# S140044_NOAA_TOWFISH.net
KiCad netlist of a schematic drawn in EAGLE
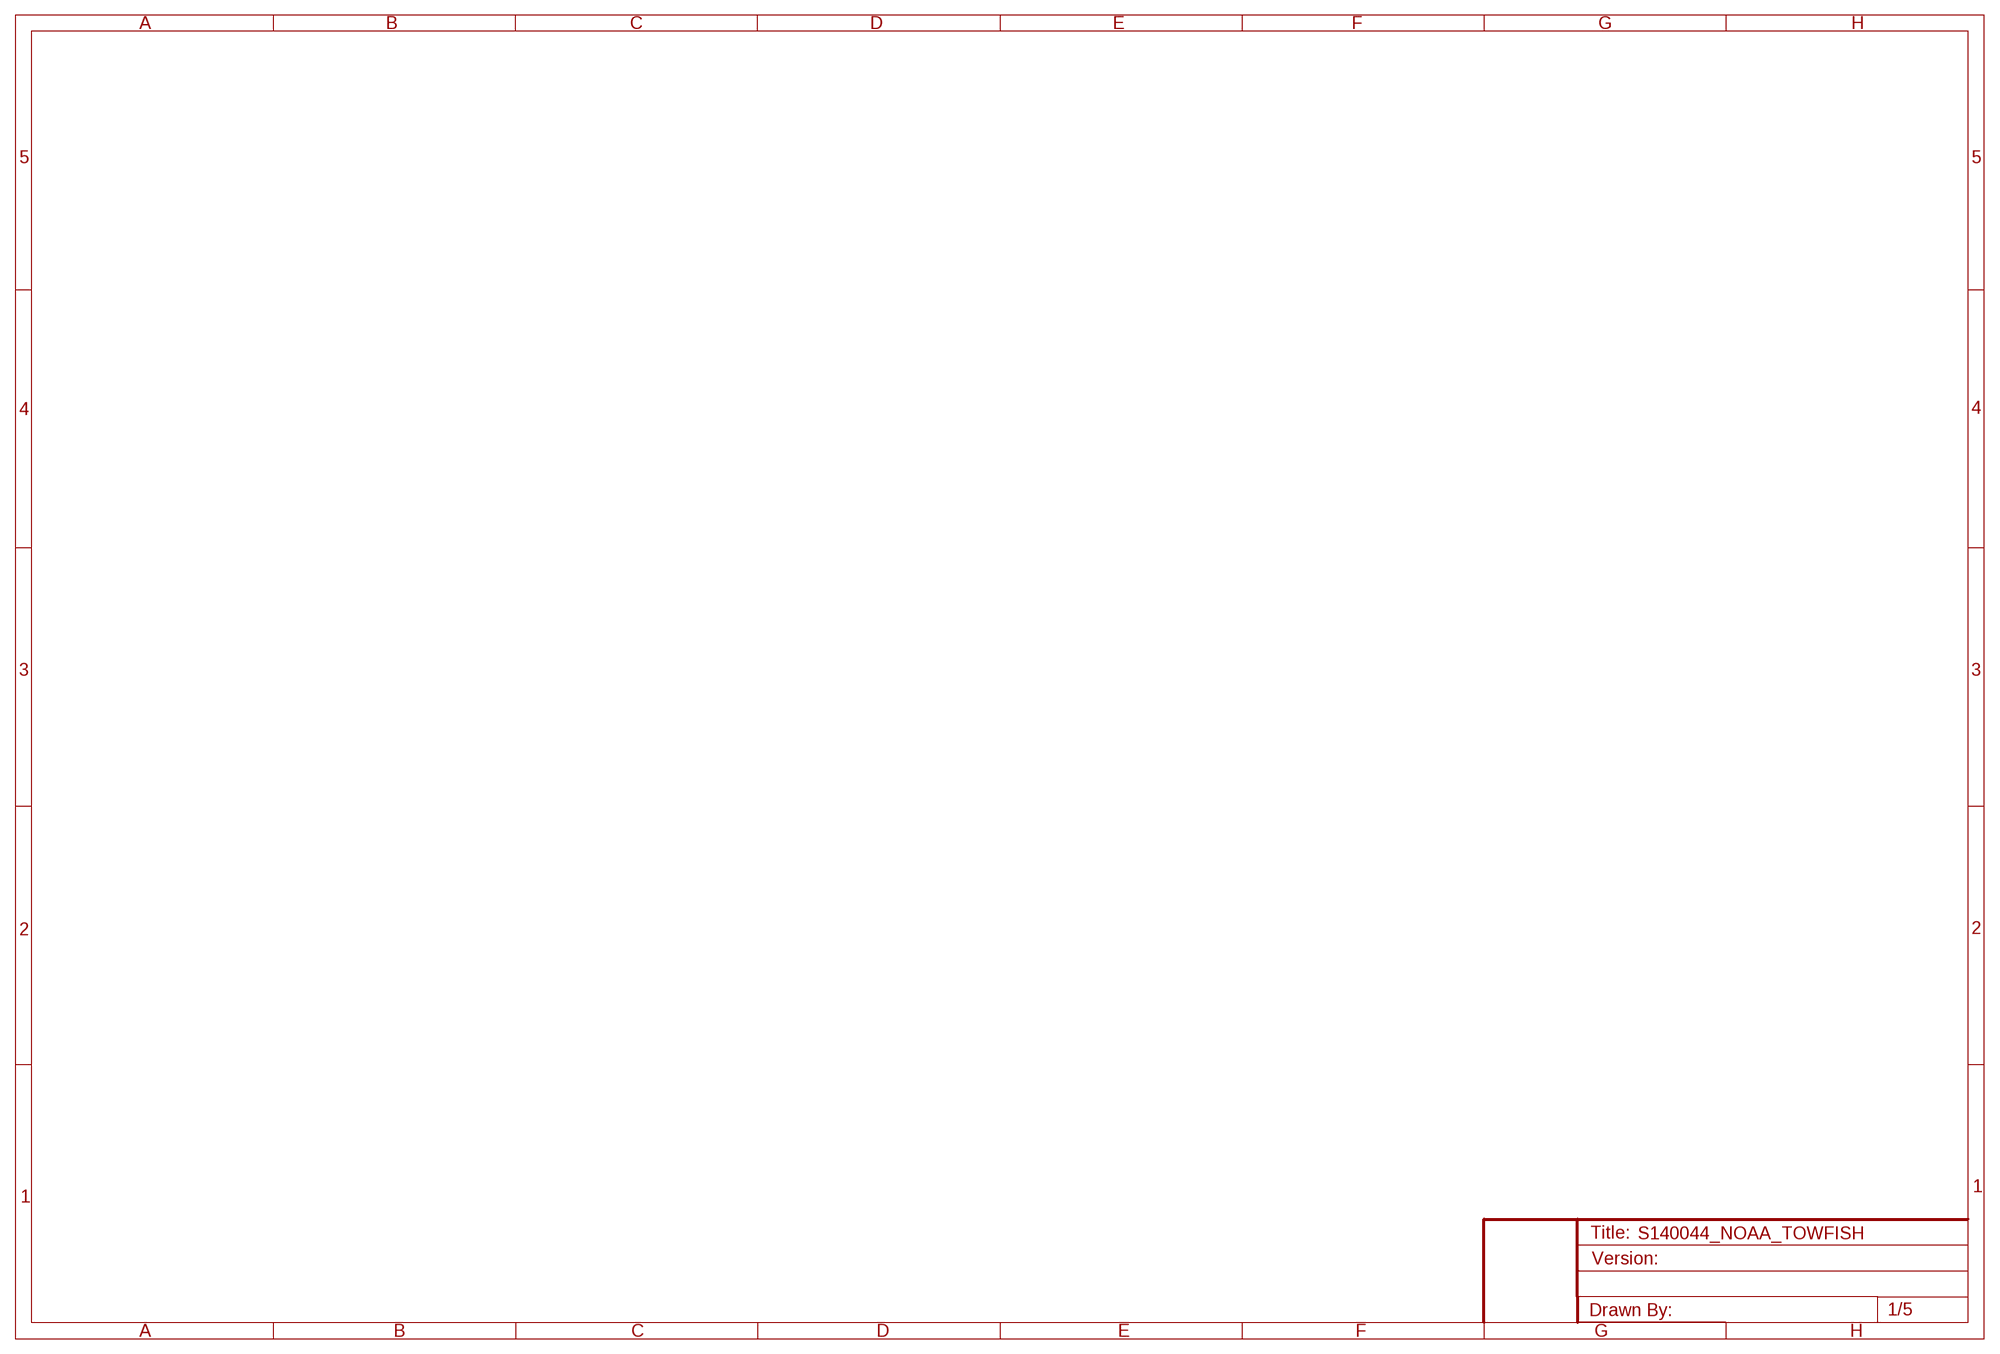
[diagram p0: schematic, sheet 1]
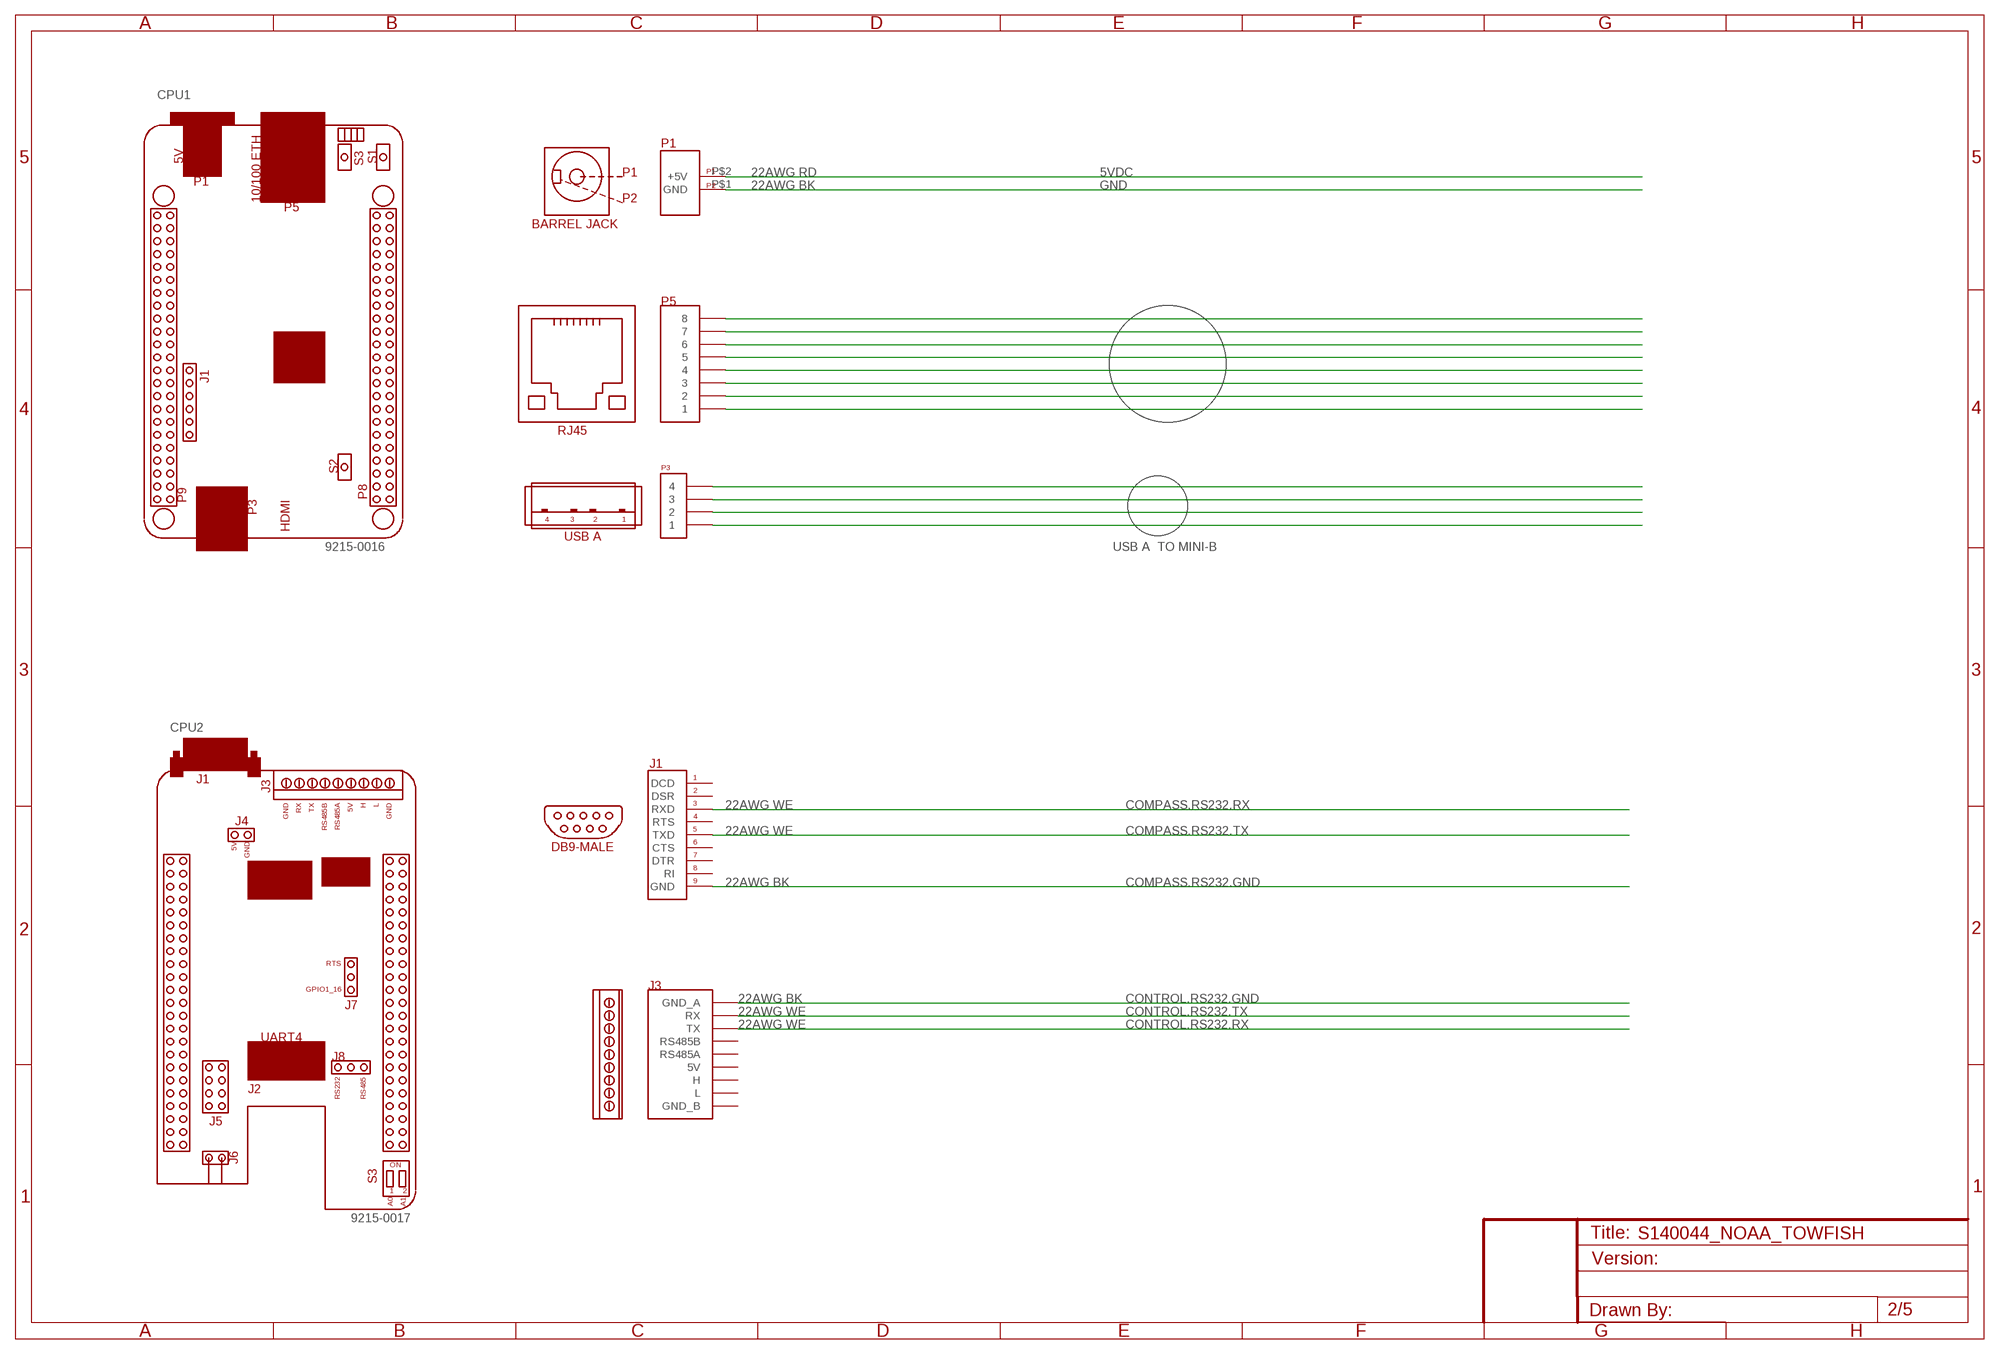
[diagram p1: schematic, sheet 2]
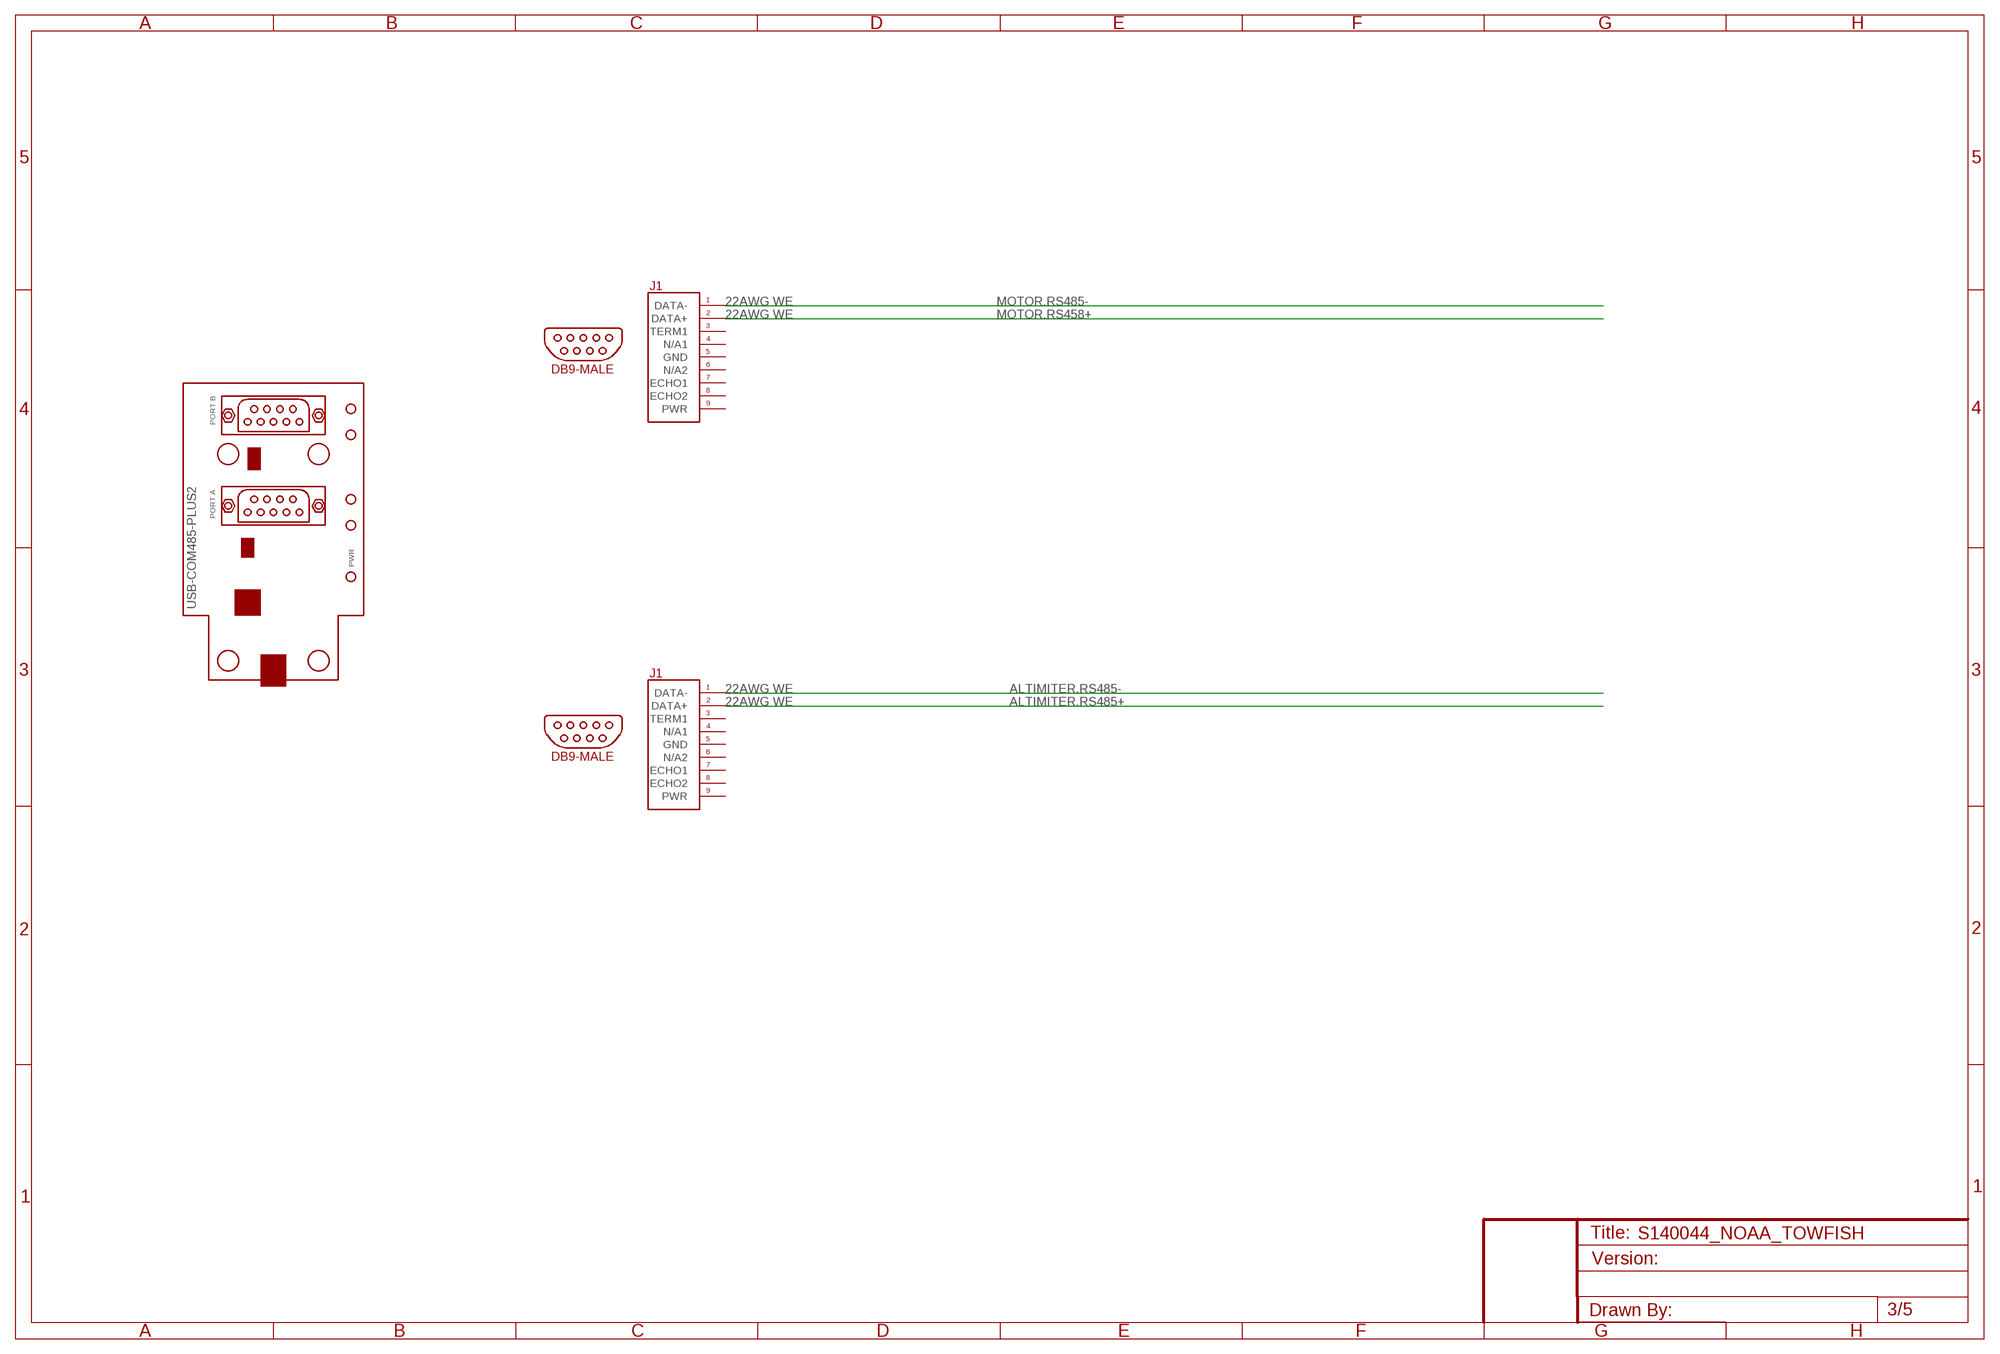
[diagram p2: schematic, sheet 3]
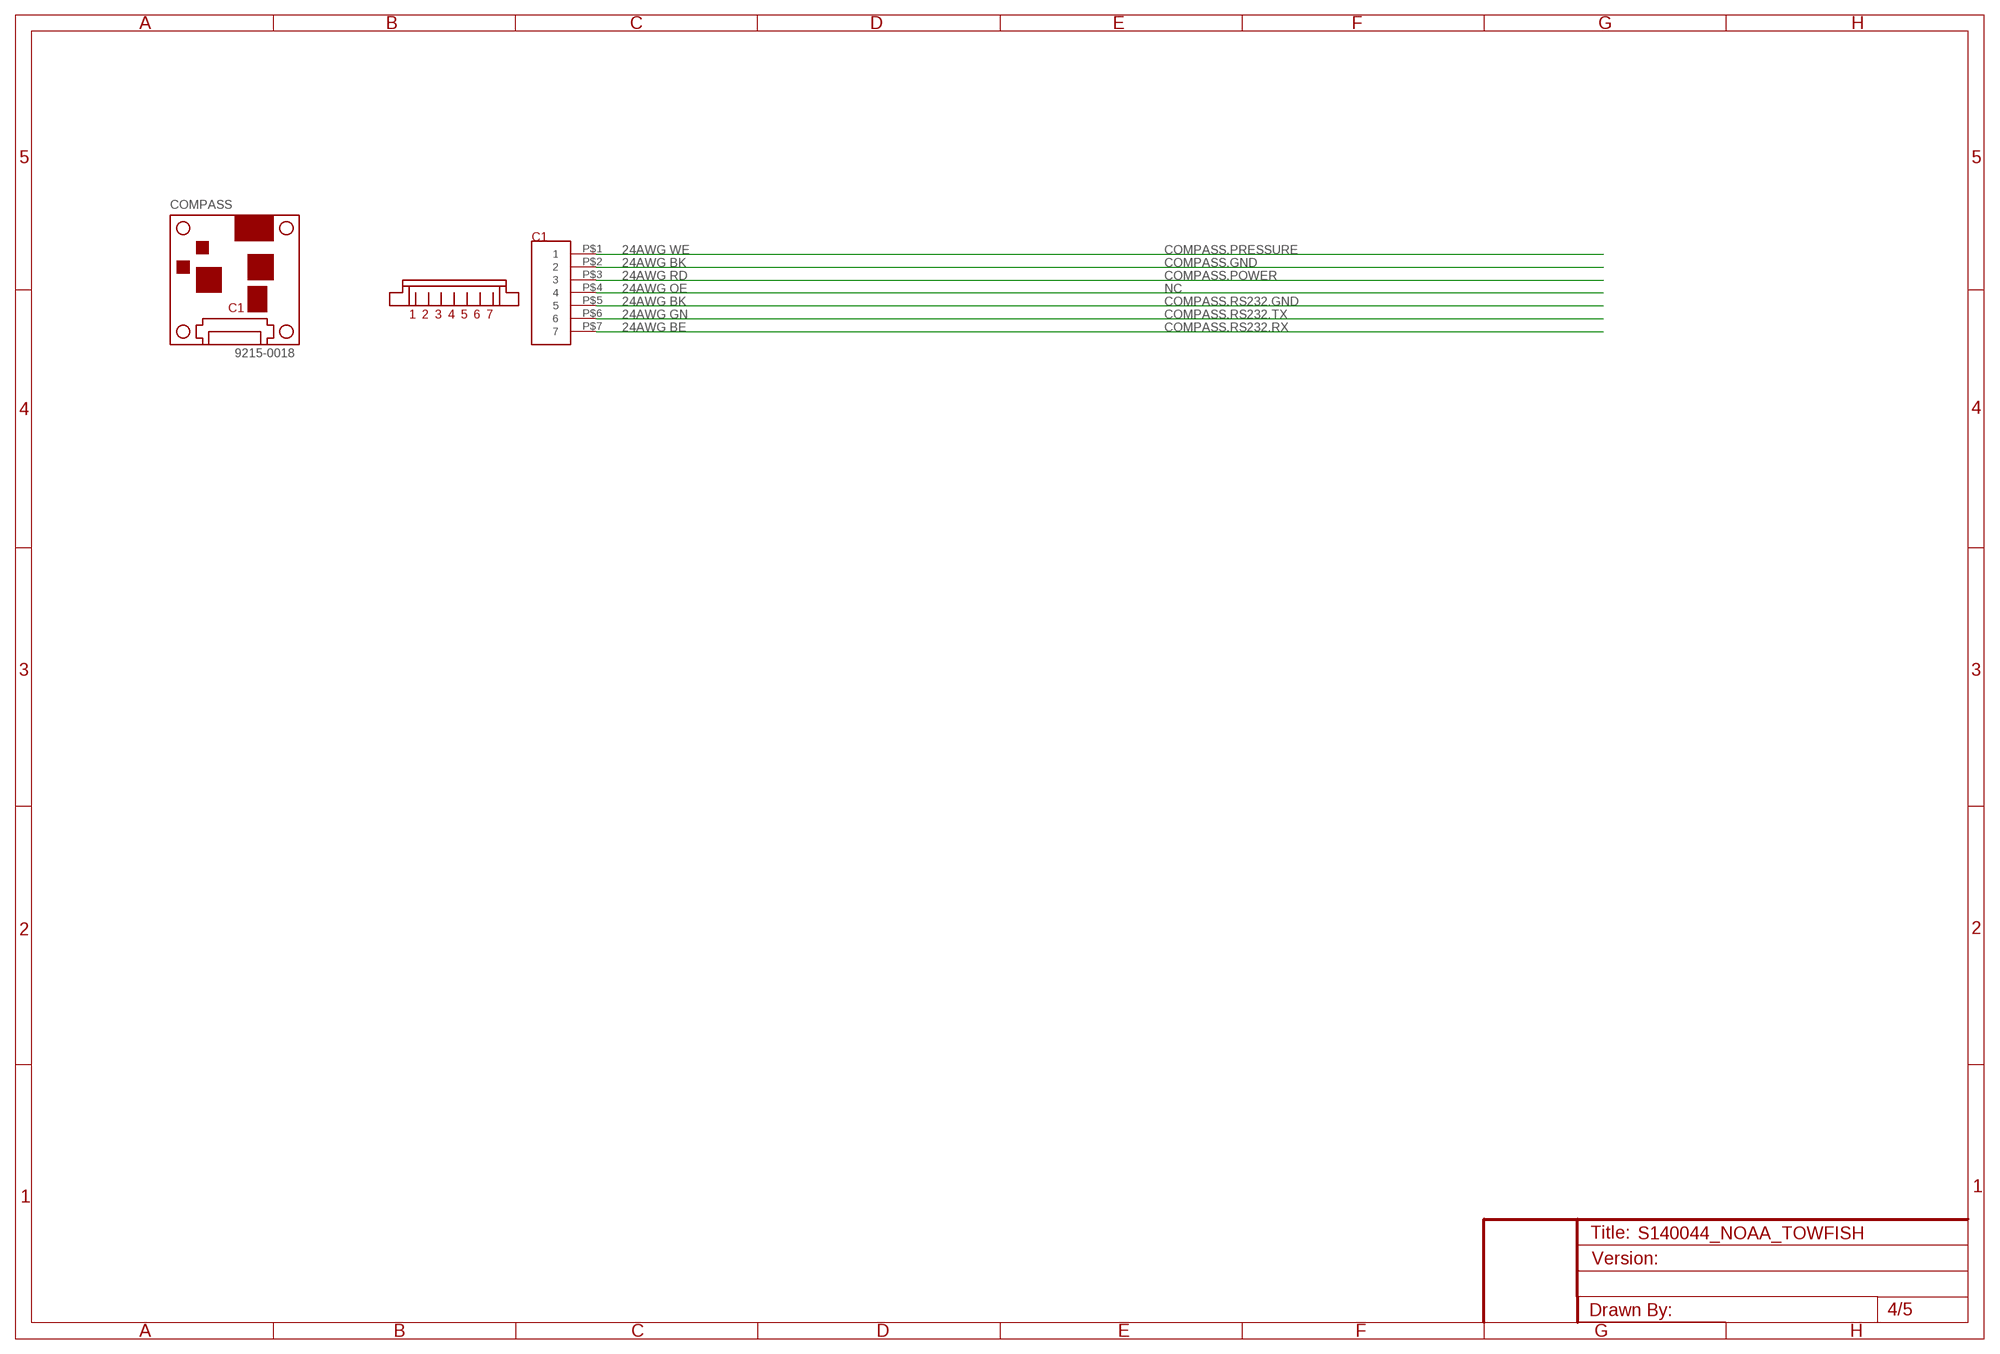
[diagram p3: schematic, sheet 4]
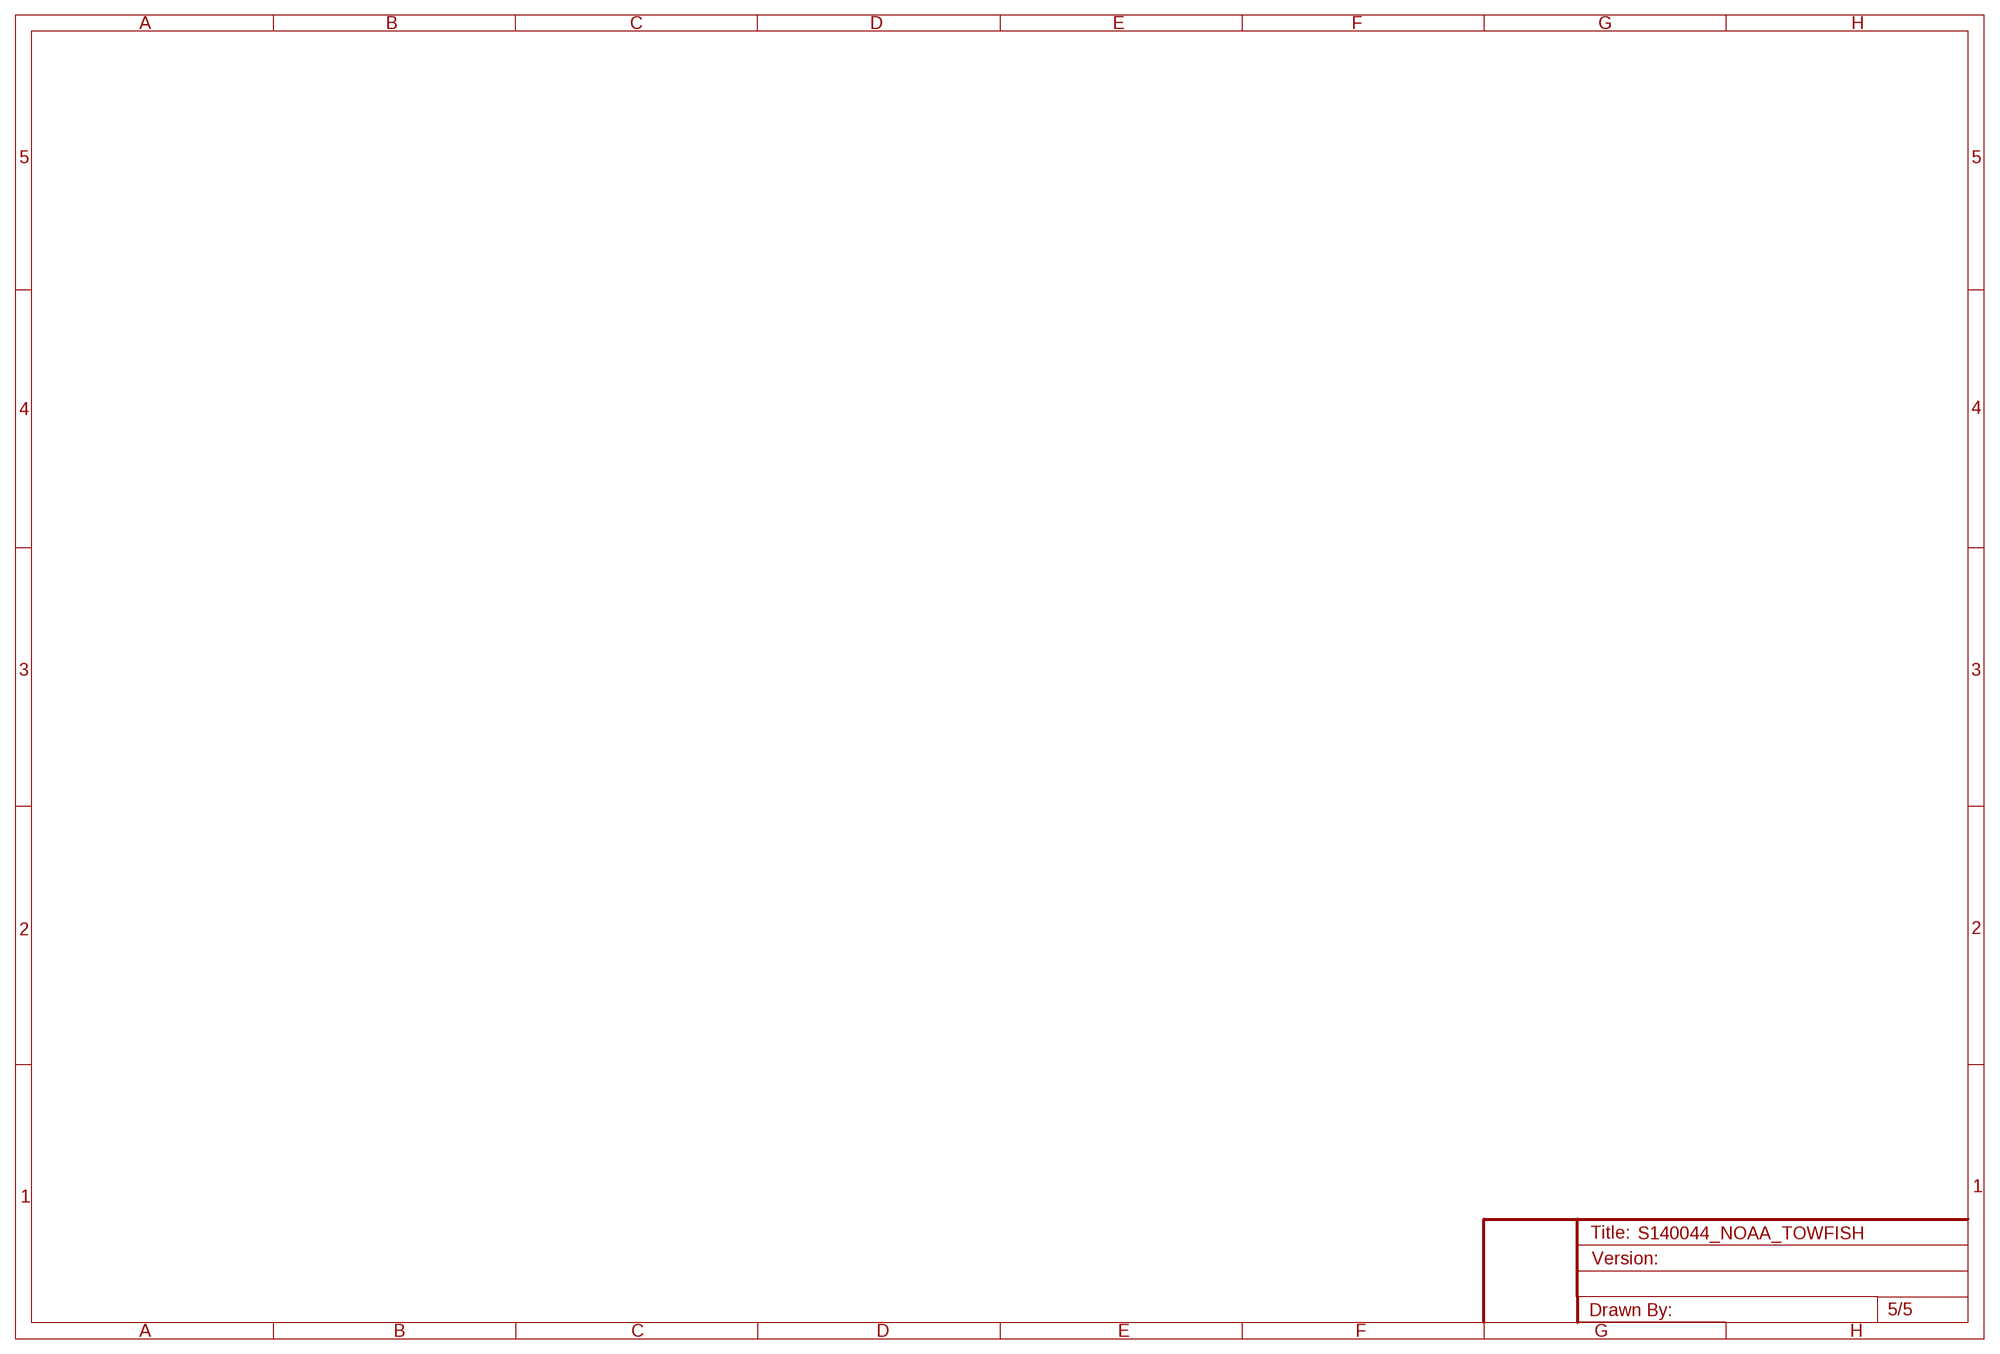
[diagram p4: schematic, sheet 5]

(export (version "E")
  (design (tool "Eeschema 10.0.6"))
  (components
    (comp (ref "U$3")
      (value "BEAGLEBONE_BLACK_P1")
      (footprint "eagle-import:BOGUS")
      (libsource (lib "eagle-import") (part "BEAGLEBONE_BLACK_P1"))
    )
    (comp (ref "U$4")
      (value "BEAGLEBONE_BLACK_P3")
      (footprint "eagle-import:BOGUS")
      (libsource (lib "eagle-import") (part "BEAGLEBONE_BLACK_P3"))
    )
    (comp (ref "U$5")
      (value "BEAGLEBONE_SERIAL_J1")
      (footprint "eagle-import:BOGUS")
      (libsource (lib "eagle-import") (part "BEAGLEBONE_SERIAL_J1"))
    )
    (comp (ref "U$6")
      (value "BEAGLEBONE_SERIAL_J3")
      (footprint "eagle-import:BOGUS")
      (libsource (lib "eagle-import") (part "BEAGLEBONE_SERIAL_J3"))
    )
    (comp (ref "U$7")
      (value "BEAGLEBONE_BLACK_P5")
      (footprint "eagle-import:BOGUS")
      (libsource (lib "eagle-import") (part "BEAGLEBONE_BLACK_P5"))
    )
    (comp (ref "U$10")
      (value "FTDI_USB_RS485_COM2")
      (footprint "eagle-import:BOGUS")
      (libsource (lib "eagle-import") (part "FTDI_USB_RS485_COM2"))
    )
    (comp (ref "U$11")
      (value "FTDI_PORTB")
      (footprint "eagle-import:BOGUS")
      (libsource (lib "eagle-import") (part "FTDI_PORTB"))
    )
    (comp (ref "U$12")
      (value "FTDI_PORTA")
      (footprint "eagle-import:BOGUS")
      (libsource (lib "eagle-import") (part "FTDI_PORTA"))
    )
    (comp (ref "U$8")
      (value "OCEANSERVER_OS5000-S_C1")
      (footprint "eagle-import:BOGUS")
      (libsource (lib "eagle-import") (part "OCEANSERVER_OS5000-S_C1"))
    )
  )
  (nets
    (net (code "1") (name "5VDC") (class "Default")
      (node (ref "U$3") (pin "P$2") (pinfunction "+5V_P$2") (pintype "bidirectional"))
    )
    (net (code "2") (name "ALTIMITER.RS485+") (class "Default")
      (node (ref "U$12") (pin "P$1") (pinfunction "DATA+_P$1") (pintype "bidirectional"))
    )
    (net (code "3") (name "ALTIMITER.RS485-") (class "Default")
      (node (ref "U$12") (pin "P$2") (pinfunction "DATA-_P$2") (pintype "bidirectional"))
    )
    (net (code "4") (name "COMPASS.GND") (class "Default")
      (node (ref "U$8") (pin "P$2") (pinfunction "2_P$2") (pintype "bidirectional"))
    )
    (net (code "5") (name "COMPASS.POWER") (class "Default")
      (node (ref "U$8") (pin "P$3") (pinfunction "3_P$3") (pintype "bidirectional"))
    )
    (net (code "6") (name "COMPASS.PRESSURE") (class "Default")
      (node (ref "U$8") (pin "P$1") (pinfunction "1_P$1") (pintype "bidirectional"))
    )
    (net (code "7") (name "COMPASS.RS232.GND") (class "Default")
      (node (ref "U$5") (pin "P$5") (pinfunction "GND_P$5") (pintype "bidirectional"))
      (node (ref "U$8") (pin "P$5") (pinfunction "5_P$5") (pintype "bidirectional"))
    )
    (net (code "8") (name "COMPASS.RS232.RX") (class "Default")
      (node (ref "U$5") (pin "P$8") (pinfunction "RXD_P$8") (pintype "bidirectional"))
      (node (ref "U$8") (pin "P$7") (pinfunction "7_P$7") (pintype "bidirectional"))
    )
    (net (code "9") (name "COMPASS.RS232.TX") (class "Default")
      (node (ref "U$5") (pin "P$9") (pinfunction "TXD_P$9") (pintype "bidirectional"))
      (node (ref "U$8") (pin "P$6") (pinfunction "6_P$6") (pintype "bidirectional"))
    )
    (net (code "10") (name "CONTROL.RS232.GND") (class "Default")
      (node (ref "U$6") (pin "P$2") (pinfunction "GND_A_P$2") (pintype "bidirectional"))
    )
    (net (code "11") (name "CONTROL.RS232.RX") (class "Default")
      (node (ref "U$6") (pin "P$9") (pinfunction "TX_P$9") (pintype "bidirectional"))
    )
    (net (code "12") (name "CONTROL.RS232.TX") (class "Default")
      (node (ref "U$6") (pin "P$8") (pinfunction "RX_P$8") (pintype "bidirectional"))
    )
    (net (code "13") (name "GND") (class "Default")
      (node (ref "U$3") (pin "P$1") (pinfunction "GND_P$1") (pintype "bidirectional"))
    )
    (net (code "14") (name "MOTOR.RS458+") (class "Default")
      (node (ref "U$11") (pin "P$1") (pinfunction "DATA+_P$1") (pintype "bidirectional"))
    )
    (net (code "15") (name "MOTOR.RS485-") (class "Default")
      (node (ref "U$11") (pin "P$2") (pinfunction "DATA-_P$2") (pintype "bidirectional"))
    )
    (net (code "16") (name "NC") (class "Default")
      (node (ref "U$8") (pin "P$4") (pinfunction "4_P$4") (pintype "bidirectional"))
    )
    (net (code "17") (name "unconnected-(U$4-1-PadP$1)") (class "Default")
      (node (ref "U$4") (pin "P$1") (pinfunction "1_P$1") (pintype "bidirectional"))
    )
    (net (code "18") (name "unconnected-(U$4-2-PadP$2)") (class "Default")
      (node (ref "U$4") (pin "P$2") (pinfunction "2_P$2") (pintype "bidirectional"))
    )
    (net (code "19") (name "unconnected-(U$4-3-PadP$3)") (class "Default")
      (node (ref "U$4") (pin "P$3") (pinfunction "3_P$3") (pintype "bidirectional"))
    )
    (net (code "20") (name "unconnected-(U$4-4-PadP$4)") (class "Default")
      (node (ref "U$4") (pin "P$4") (pinfunction "4_P$4") (pintype "bidirectional"))
    )
    (net (code "21") (name "unconnected-(U$5-CTS-PadP$1)") (class "Default")
      (node (ref "U$5") (pin "P$1") (pinfunction "CTS_P$1") (pintype "bidirectional"))
    )
    (net (code "22") (name "unconnected-(U$5-DCD-PadP$2)") (class "Default")
      (node (ref "U$5") (pin "P$2") (pinfunction "DCD_P$2") (pintype "bidirectional"))
    )
    (net (code "23") (name "unconnected-(U$5-DSR-PadP$3)") (class "Default")
      (node (ref "U$5") (pin "P$3") (pinfunction "DSR_P$3") (pintype "bidirectional"))
    )
    (net (code "24") (name "unconnected-(U$5-DTR-PadP$4)") (class "Default")
      (node (ref "U$5") (pin "P$4") (pinfunction "DTR_P$4") (pintype "bidirectional"))
    )
    (net (code "25") (name "unconnected-(U$5-RI-PadP$6)") (class "Default")
      (node (ref "U$5") (pin "P$6") (pinfunction "RI_P$6") (pintype "bidirectional"))
    )
    (net (code "26") (name "unconnected-(U$5-RTS-PadP$7)") (class "Default")
      (node (ref "U$5") (pin "P$7") (pinfunction "RTS_P$7") (pintype "bidirectional"))
    )
    (net (code "27") (name "unconnected-(U$6-5V-PadP$1)") (class "Default")
      (node (ref "U$6") (pin "P$1") (pinfunction "5V_P$1") (pintype "bidirectional"))
    )
    (net (code "28") (name "unconnected-(U$6-GND_B-PadP$3)") (class "Default")
      (node (ref "U$6") (pin "P$3") (pinfunction "GND_B_P$3") (pintype "bidirectional"))
    )
    (net (code "29") (name "unconnected-(U$6-H-PadP$4)") (class "Default")
      (node (ref "U$6") (pin "P$4") (pinfunction "H_P$4") (pintype "bidirectional"))
    )
    (net (code "30") (name "unconnected-(U$6-L-PadP$5)") (class "Default")
      (node (ref "U$6") (pin "P$5") (pinfunction "L_P$5") (pintype "bidirectional"))
    )
    (net (code "31") (name "unconnected-(U$6-RS485A-PadP$6)") (class "Default")
      (node (ref "U$6") (pin "P$6") (pinfunction "RS485A_P$6") (pintype "bidirectional"))
    )
    (net (code "32") (name "unconnected-(U$6-RS485B-PadP$7)") (class "Default")
      (node (ref "U$6") (pin "P$7") (pinfunction "RS485B_P$7") (pintype "bidirectional"))
    )
    (net (code "33") (name "unconnected-(U$7-1-PadP$1)") (class "Default")
      (node (ref "U$7") (pin "P$1") (pinfunction "1_P$1") (pintype "bidirectional"))
    )
    (net (code "34") (name "unconnected-(U$7-2-PadP$2)") (class "Default")
      (node (ref "U$7") (pin "P$2") (pinfunction "2_P$2") (pintype "bidirectional"))
    )
    (net (code "35") (name "unconnected-(U$7-3-PadP$3)") (class "Default")
      (node (ref "U$7") (pin "P$3") (pinfunction "3_P$3") (pintype "bidirectional"))
    )
    (net (code "36") (name "unconnected-(U$7-4-PadP$4)") (class "Default")
      (node (ref "U$7") (pin "P$4") (pinfunction "4_P$4") (pintype "bidirectional"))
    )
    (net (code "37") (name "unconnected-(U$7-5-PadP$5)") (class "Default")
      (node (ref "U$7") (pin "P$5") (pinfunction "5_P$5") (pintype "bidirectional"))
    )
    (net (code "38") (name "unconnected-(U$7-6-PadP$6)") (class "Default")
      (node (ref "U$7") (pin "P$6") (pinfunction "6_P$6") (pintype "bidirectional"))
    )
    (net (code "39") (name "unconnected-(U$7-7-PadP$7)") (class "Default")
      (node (ref "U$7") (pin "P$7") (pinfunction "7_P$7") (pintype "bidirectional"))
    )
    (net (code "40") (name "unconnected-(U$7-8-PadP$8)") (class "Default")
      (node (ref "U$7") (pin "P$8") (pinfunction "8_P$8") (pintype "bidirectional"))
    )
    (net (code "41") (name "unconnected-(U$11-ECHO1-PadP$3)") (class "Default")
      (node (ref "U$11") (pin "P$3") (pinfunction "ECHO1_P$3") (pintype "bidirectional"))
    )
    (net (code "42") (name "unconnected-(U$11-ECHO2-PadP$4)") (class "Default")
      (node (ref "U$11") (pin "P$4") (pinfunction "ECHO2_P$4") (pintype "bidirectional"))
    )
    (net (code "43") (name "unconnected-(U$11-GND-PadP$5)") (class "Default")
      (node (ref "U$11") (pin "P$5") (pinfunction "GND_P$5") (pintype "bidirectional"))
    )
    (net (code "44") (name "unconnected-(U$11-N{slash}A1-PadP$6)") (class "Default")
      (node (ref "U$11") (pin "P$6") (pinfunction "N/A1_P$6") (pintype "bidirectional"))
    )
    (net (code "45") (name "unconnected-(U$11-N{slash}A2-PadP$7)") (class "Default")
      (node (ref "U$11") (pin "P$7") (pinfunction "N/A2_P$7") (pintype "bidirectional"))
    )
    (net (code "46") (name "unconnected-(U$11-PWR-PadP$8)") (class "Default")
      (node (ref "U$11") (pin "P$8") (pinfunction "PWR_P$8") (pintype "bidirectional"))
    )
    (net (code "47") (name "unconnected-(U$11-TERM1-PadP$9)") (class "Default")
      (node (ref "U$11") (pin "P$9") (pinfunction "TERM1_P$9") (pintype "bidirectional"))
    )
    (net (code "48") (name "unconnected-(U$12-ECHO1-PadP$3)") (class "Default")
      (node (ref "U$12") (pin "P$3") (pinfunction "ECHO1_P$3") (pintype "bidirectional"))
    )
    (net (code "49") (name "unconnected-(U$12-ECHO2-PadP$4)") (class "Default")
      (node (ref "U$12") (pin "P$4") (pinfunction "ECHO2_P$4") (pintype "bidirectional"))
    )
    (net (code "50") (name "unconnected-(U$12-GND-PadP$5)") (class "Default")
      (node (ref "U$12") (pin "P$5") (pinfunction "GND_P$5") (pintype "bidirectional"))
    )
    (net (code "51") (name "unconnected-(U$12-N{slash}A1-PadP$6)") (class "Default")
      (node (ref "U$12") (pin "P$6") (pinfunction "N/A1_P$6") (pintype "bidirectional"))
    )
    (net (code "52") (name "unconnected-(U$12-N{slash}A2-PadP$7)") (class "Default")
      (node (ref "U$12") (pin "P$7") (pinfunction "N/A2_P$7") (pintype "bidirectional"))
    )
    (net (code "53") (name "unconnected-(U$12-PWR-PadP$8)") (class "Default")
      (node (ref "U$12") (pin "P$8") (pinfunction "PWR_P$8") (pintype "bidirectional"))
    )
    (net (code "54") (name "unconnected-(U$12-TERM1-PadP$9)") (class "Default")
      (node (ref "U$12") (pin "P$9") (pinfunction "TERM1_P$9") (pintype "bidirectional"))
    )
  )
)
